# LaunchPad_eZFET_1_4.net
KiCad netlist of a schematic drawn in Altium Designer
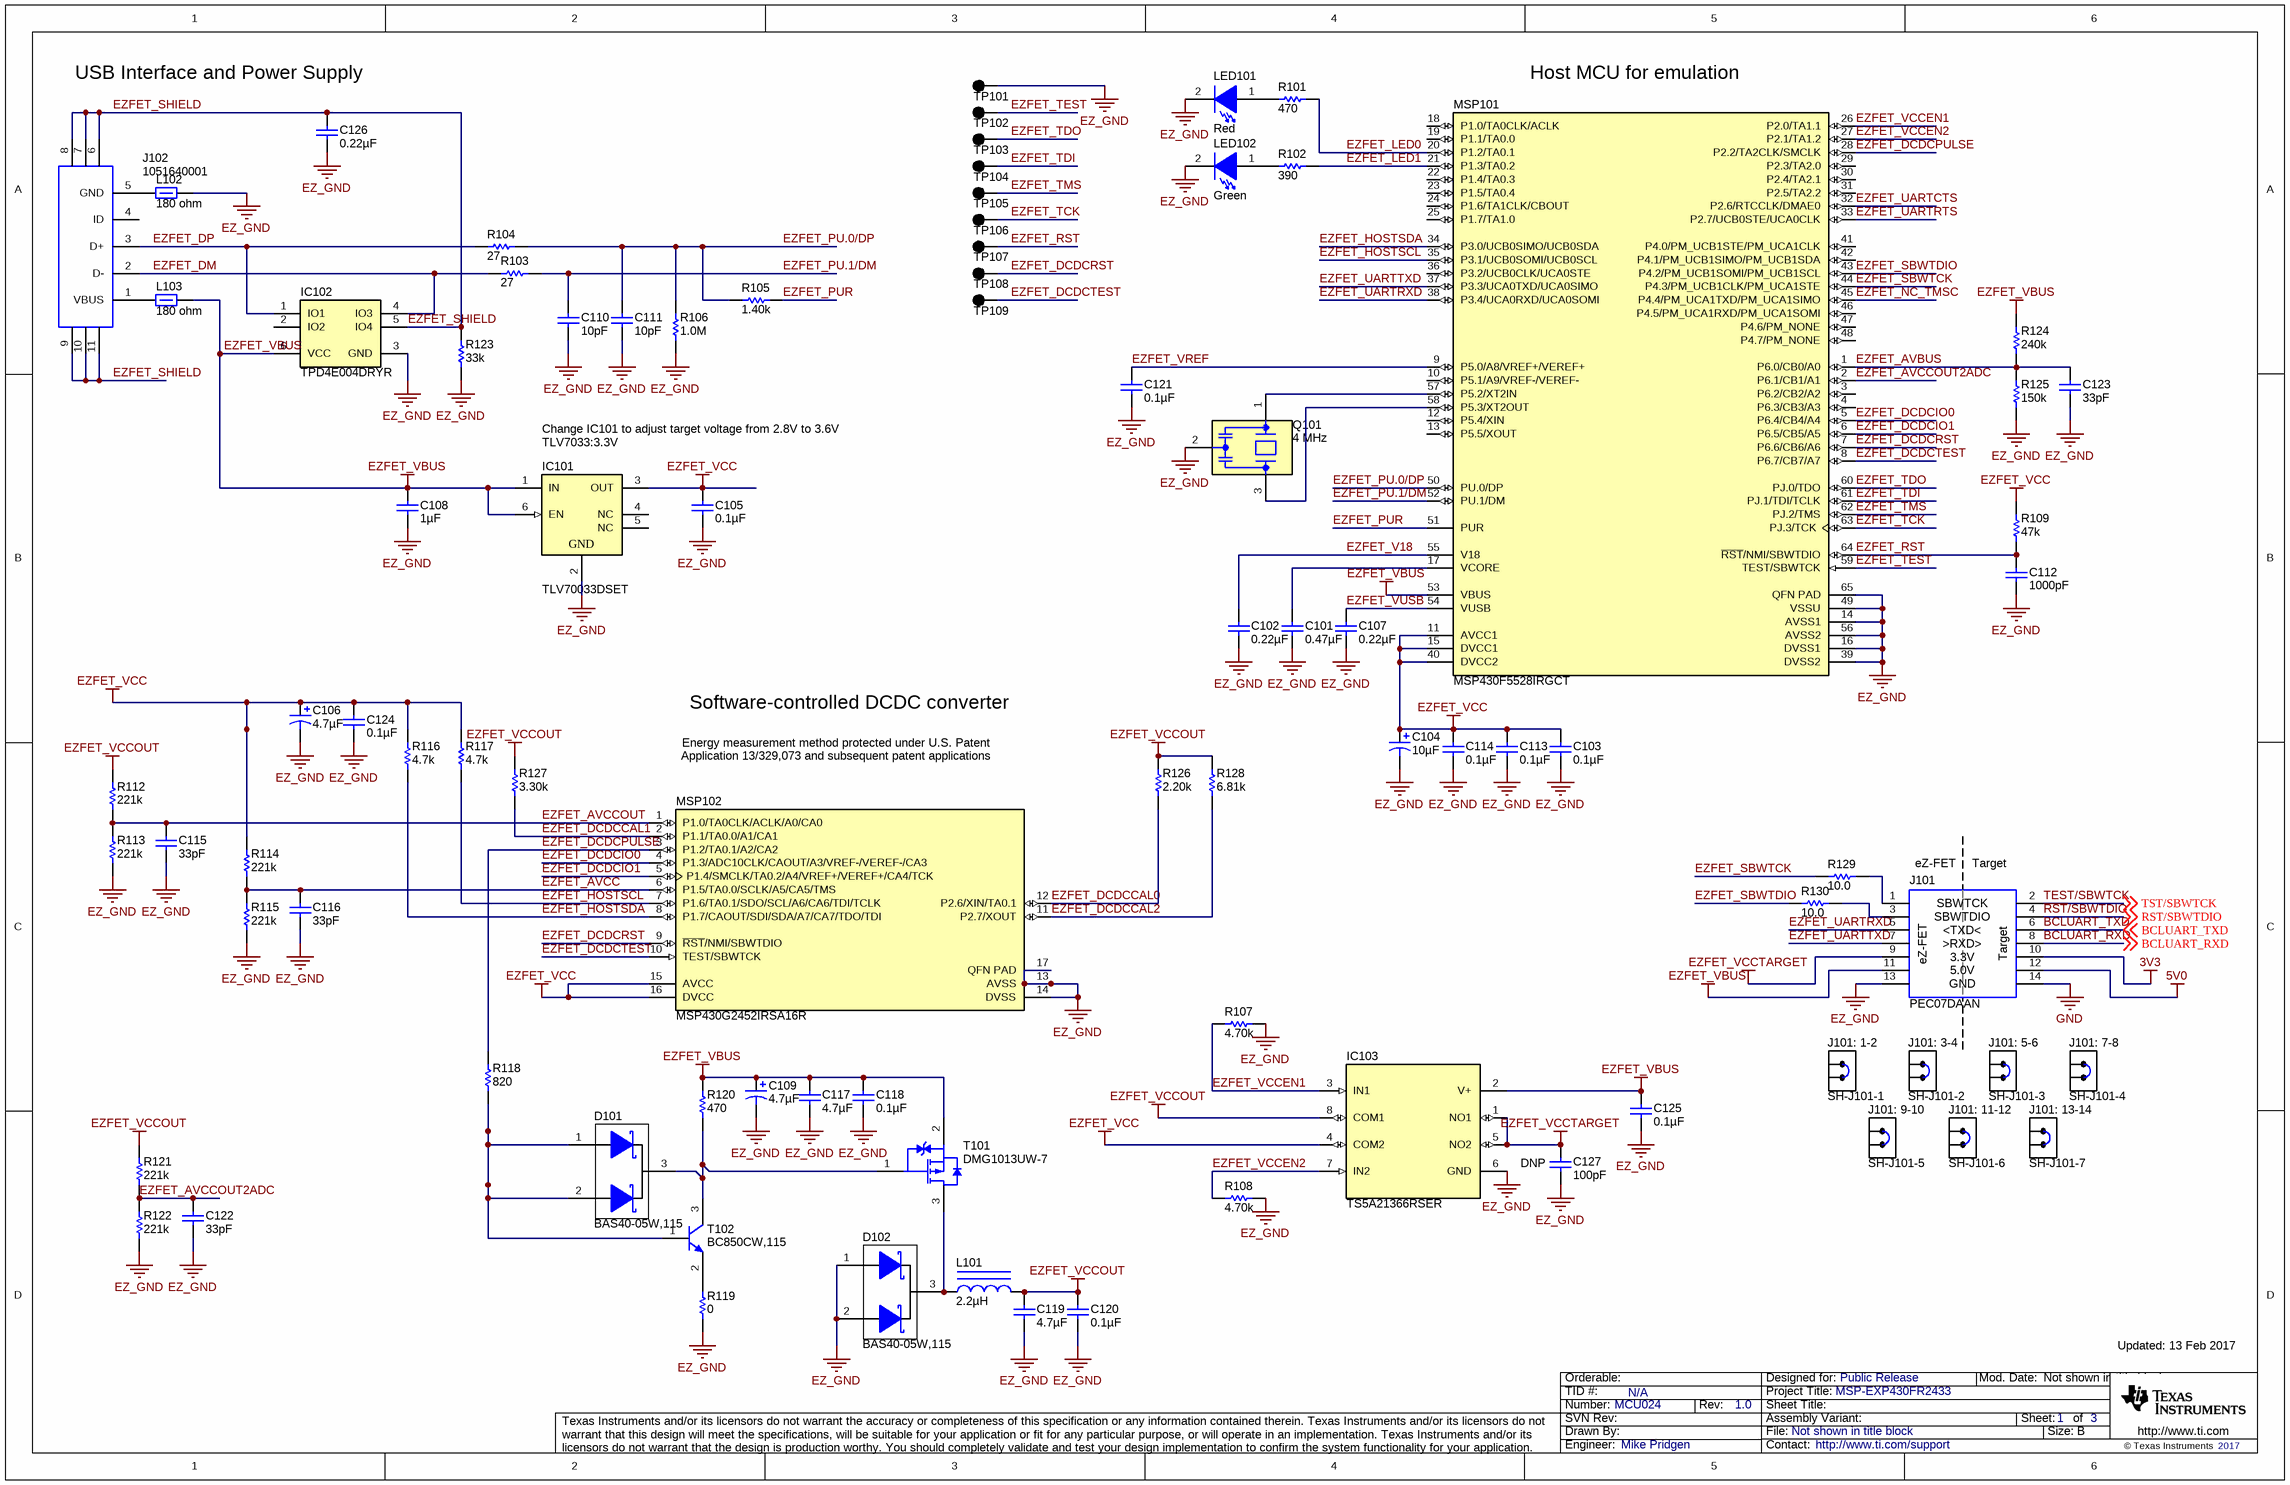
[diagram p0: LaunchPad_eZFET_1.4.SchDoc]

(export (version "E")
  (design (tool "Eeschema 10.0.6"))
  (components
    (comp (ref "C101")
      (value "GRM155R61C474KE01")
      (footprint "0402")
      (description "CAP, CERM, 0.47 µF, 16 V, +/- 10%, X5R, 0402")
      (fields
        (field (name "VALUEDISPLAYED") "0.47µF")
        (field (name "MANUFACTURER") "MuRata")
        (field (name "PUBLISHER") "Texas Instruments")
      )
      (libsource (lib "Capacitor_Ceramic") (part "GRM155R61C474KE01"))
    )
    (comp (ref "C102")
      (value "GRM188R61C224KA88D")
      (footprint "0603")
      (description "CAP, CERM, 0.22 µF, 16 V, +/- 10%, X5R, 0603")
      (fields
        (field (name "VALUEDISPLAYED") "0.22µF")
        (field (name "MANUFACTURER") "MuRata")
        (field (name "PUBLISHER") "Texas Instruments")
      )
      (libsource (lib "Capacitor_Ceramic") (part "GRM188R61C224KA88D"))
    )
    (comp (ref "C103")
      (value "GRM155R61A104KA01D")
      (footprint "0402")
      (description "CAP, CERM, 0.1 µF, 10 V, +/- 10%, X5R, 0402")
      (fields
        (field (name "VALUEDISPLAYED") "0.1µF")
        (field (name "MANUFACTURER") "MuRata")
        (field (name "PUBLISHER") "Texas Instruments")
      )
      (libsource (lib "Capacitor_Ceramic") (part "GRM155R61A104KA01D"))
    )
    (comp (ref "C104")
      (value "293D106X0010A2TE3")
      (footprint "3216-18")
      (description "CAP, TA, 10 µF, 10 V, +/- 20%, 3.4 ohm, SMD")
      (fields
        (field (name "VALUEDISPLAYED") "10µF")
        (field (name "MANUFACTURER") "Vishay-Sprague")
        (field (name "PUBLISHER") "Texas Instruments")
      )
      (libsource (lib "Capacitor_Tantalum") (part "293D106X0010A2TE3"))
    )
    (comp (ref "C105")
      (value "GRM155R61A104KA01D")
      (footprint "0402")
      (description "CAP, CERM, 0.1 µF, 10 V, +/- 10%, X5R, 0402")
      (fields
        (field (name "VALUEDISPLAYED") "0.1µF")
        (field (name "MANUFACTURER") "MuRata")
        (field (name "PUBLISHER") "Texas Instruments")
      )
      (libsource (lib "Capacitor_Ceramic") (part "GRM155R61A104KA01D"))
    )
    (comp (ref "C106")
      (value "293D475X9010A2TE3")
      (footprint "3216-18")
      (description "CAP, TA, 4.7 µF, 10 V, +/- 10%, 5 ohm, SMD")
      (fields
        (field (name "VALUEDISPLAYED") "4.7µF")
        (field (name "MANUFACTURER") "Vishay-Sprague")
        (field (name "PUBLISHER") "Texas Instruments")
      )
      (libsource (lib "Capacitor_Tantalum") (part "293D475X9010A2TE3"))
    )
    (comp (ref "C107")
      (value "GRM188R61C224KA88D")
      (footprint "0603")
      (description "CAP, CERM, 0.22 µF, 16 V, +/- 10%, X5R, 0603")
      (fields
        (field (name "VALUEDISPLAYED") "0.22µF")
        (field (name "MANUFACTURER") "MuRata")
        (field (name "PUBLISHER") "Texas Instruments")
      )
      (libsource (lib "Capacitor_Ceramic") (part "GRM188R61C224KA88D"))
    )
    (comp (ref "C108")
      (value "GRM185R61A105KE36D")
      (footprint "0603")
      (description "CAP, CERM, 1 µF, 10 V, +/- 10%, X5R, 0603")
      (fields
        (field (name "VALUEDISPLAYED") "1µF")
        (field (name "MANUFACTURER") "MuRata")
        (field (name "PUBLISHER") "Texas Instruments")
      )
      (libsource (lib "Capacitor_Ceramic") (part "GRM185R61A105KE36D"))
    )
    (comp (ref "C109")
      (value "293D475X9010A2TE3")
      (footprint "3216-18")
      (description "CAP, TA, 4.7 µF, 10 V, +/- 10%, 5 ohm, SMD")
      (fields
        (field (name "VALUEDISPLAYED") "4.7µF")
        (field (name "MANUFACTURER") "Vishay-Sprague")
        (field (name "PUBLISHER") "Texas Instruments")
      )
      (libsource (lib "Capacitor_Tantalum") (part "293D475X9010A2TE3"))
    )
    (comp (ref "C110")
      (value "GRM1555C1H100JA01D")
      (footprint "0402")
      (description "CAP, CERM, 10 pF, 50 V, +/- 5%, C0G/NP0, 0402")
      (fields
        (field (name "VALUEDISPLAYED") "10pF")
        (field (name "MANUFACTURER") "MuRata")
        (field (name "PUBLISHER") "Texas Instruments")
      )
      (libsource (lib "Capacitor_Ceramic") (part "GRM1555C1H100JA01D"))
    )
    (comp (ref "C111")
      (value "GRM1555C1H100JA01D")
      (footprint "0402")
      (description "CAP, CERM, 10 pF, 50 V, +/- 5%, C0G/NP0, 0402")
      (fields
        (field (name "VALUEDISPLAYED") "10pF")
        (field (name "MANUFACTURER") "MuRata")
        (field (name "PUBLISHER") "Texas Instruments")
      )
      (libsource (lib "Capacitor_Ceramic") (part "GRM1555C1H100JA01D"))
    )
    (comp (ref "C112")
      (value "GRM155R71H102KA01D")
      (footprint "0402")
      (description "CAP, CERM, 1000 pF, 50 V, +/- 10%, X7R, 0402")
      (fields
        (field (name "VALUEDISPLAYED") "1000pF")
        (field (name "MANUFACTURER") "MuRata")
        (field (name "PUBLISHER") "Texas Instruments")
      )
      (libsource (lib "Capacitor_Ceramic") (part "GRM155R71H102KA01D"))
    )
    (comp (ref "C113")
      (value "GRM155R61A104KA01D")
      (footprint "0402")
      (description "CAP, CERM, 0.1 µF, 10 V, +/- 10%, X5R, 0402")
      (fields
        (field (name "VALUEDISPLAYED") "0.1µF")
        (field (name "MANUFACTURER") "MuRata")
        (field (name "PUBLISHER") "Texas Instruments")
      )
      (libsource (lib "Capacitor_Ceramic") (part "GRM155R61A104KA01D"))
    )
    (comp (ref "C114")
      (value "GRM155R61A104KA01D")
      (footprint "0402")
      (description "CAP, CERM, 0.1 µF, 10 V, +/- 10%, X5R, 0402")
      (fields
        (field (name "VALUEDISPLAYED") "0.1µF")
        (field (name "MANUFACTURER") "MuRata")
        (field (name "PUBLISHER") "Texas Instruments")
      )
      (libsource (lib "Capacitor_Ceramic") (part "GRM155R61A104KA01D"))
    )
    (comp (ref "C115")
      (value "GRM1555C1H330JA01D")
      (footprint "0402")
      (description "CAP, CERM, 33 pF, 50 V, +/- 5%, C0G/NP0, 0402")
      (fields
        (field (name "VALUEDISPLAYED") "33pF")
        (field (name "MANUFACTURER") "MuRata")
        (field (name "PUBLISHER") "Texas Instruments")
      )
      (libsource (lib "Capacitor_Ceramic") (part "GRM1555C1H330JA01D"))
    )
    (comp (ref "C116")
      (value "GRM1555C1H330JA01D")
      (footprint "0402")
      (description "CAP, CERM, 33 pF, 50 V, +/- 5%, C0G/NP0, 0402")
      (fields
        (field (name "VALUEDISPLAYED") "33pF")
        (field (name "MANUFACTURER") "MuRata")
        (field (name "PUBLISHER") "Texas Instruments")
      )
      (libsource (lib "Capacitor_Ceramic") (part "GRM1555C1H330JA01D"))
    )
    (comp (ref "C117")
      (value "GRM188R61C475KAAJ")
      (footprint "0603")
      (description "CAP, CERM, 4.7 µF, 16 V, +/- 10%, X5R, 0603")
      (fields
        (field (name "VALUEDISPLAYED") "4.7µF")
        (field (name "MANUFACTURER") "MuRata")
        (field (name "PUBLISHER") "Texas Instruments")
      )
      (libsource (lib "Capacitor_Ceramic") (part "GRM188R61C475KAAJ"))
    )
    (comp (ref "C118")
      (value "GRM155R61A104KA01D")
      (footprint "0402")
      (description "CAP, CERM, 0.1 µF, 10 V, +/- 10%, X5R, 0402")
      (fields
        (field (name "VALUEDISPLAYED") "0.1µF")
        (field (name "MANUFACTURER") "MuRata")
        (field (name "PUBLISHER") "Texas Instruments")
      )
      (libsource (lib "Capacitor_Ceramic") (part "GRM155R61A104KA01D"))
    )
    (comp (ref "C119")
      (value "GRM188R61C475KAAJ")
      (footprint "0603")
      (description "CAP, CERM, 4.7 µF, 16 V, +/- 10%, X5R, 0603")
      (fields
        (field (name "VALUEDISPLAYED") "4.7µF")
        (field (name "MANUFACTURER") "MuRata")
        (field (name "PUBLISHER") "Texas Instruments")
      )
      (libsource (lib "Capacitor_Ceramic") (part "GRM188R61C475KAAJ"))
    )
    (comp (ref "C120")
      (value "GRM155R61A104KA01D")
      (footprint "0402")
      (description "CAP, CERM, 0.1 µF, 10 V, +/- 10%, X5R, 0402")
      (fields
        (field (name "VALUEDISPLAYED") "0.1µF")
        (field (name "MANUFACTURER") "MuRata")
        (field (name "PUBLISHER") "Texas Instruments")
      )
      (libsource (lib "Capacitor_Ceramic") (part "GRM155R61A104KA01D"))
    )
    (comp (ref "C121")
      (value "GRM155R61A104KA01D")
      (footprint "0402")
      (description "CAP, CERM, 0.1 µF, 10 V, +/- 10%, X5R, 0402")
      (fields
        (field (name "VALUEDISPLAYED") "0.1µF")
        (field (name "MANUFACTURER") "MuRata")
        (field (name "PUBLISHER") "Texas Instruments")
      )
      (libsource (lib "Capacitor_Ceramic") (part "GRM155R61A104KA01D"))
    )
    (comp (ref "C122")
      (value "GRM1555C1H330JA01D")
      (footprint "0402")
      (description "CAP, CERM, 33 pF, 50 V, +/- 5%, C0G/NP0, 0402")
      (fields
        (field (name "VALUEDISPLAYED") "33pF")
        (field (name "MANUFACTURER") "MuRata")
        (field (name "PUBLISHER") "Texas Instruments")
      )
      (libsource (lib "Capacitor_Ceramic") (part "GRM1555C1H330JA01D"))
    )
    (comp (ref "C123")
      (value "GRM1555C1H330JA01D")
      (footprint "0402")
      (description "CAP, CERM, 33 pF, 50 V, +/- 5%, C0G/NP0, 0402")
      (fields
        (field (name "VALUEDISPLAYED") "33pF")
        (field (name "MANUFACTURER") "MuRata")
        (field (name "PUBLISHER") "Texas Instruments")
      )
      (libsource (lib "Capacitor_Ceramic") (part "GRM1555C1H330JA01D"))
    )
    (comp (ref "C124")
      (value "GRM155R61A104KA01D")
      (footprint "0402")
      (description "CAP, CERM, 0.1 µF, 10 V, +/- 10%, X5R, 0402")
      (fields
        (field (name "VALUEDISPLAYED") "0.1µF")
        (field (name "MANUFACTURER") "MuRata")
        (field (name "PUBLISHER") "Texas Instruments")
      )
      (libsource (lib "Capacitor_Ceramic") (part "GRM155R61A104KA01D"))
    )
    (comp (ref "C125")
      (value "GRM155R61A104KA01D")
      (footprint "0402")
      (description "CAP, CERM, 0.1 µF, 10 V, +/- 10%, X5R, 0402")
      (fields
        (field (name "VALUEDISPLAYED") "0.1µF")
        (field (name "MANUFACTURER") "MuRata")
        (field (name "PUBLISHER") "Texas Instruments")
      )
      (libsource (lib "Capacitor_Ceramic") (part "GRM155R61A104KA01D"))
    )
    (comp (ref "C126")
      (value "GRM155R61A224KE19D")
      (footprint "0402")
      (description "CAP, CERM, 0.22 µF, 10 V, +/- 10%, X5R, 0402")
      (fields
        (field (name "VALUEDISPLAYED") "0.22µF")
        (field (name "MANUFACTURER") "MuRata")
        (field (name "PUBLISHER") "Texas Instruments")
      )
      (libsource (lib "Capacitor_Ceramic") (part "GRM155R61A224KE19D"))
    )
    (comp (ref "C127")
      (value "GRM1555C1H101JA01D")
      (footprint "0402")
      (description "CAP, CERM, 100 pF, 50 V, +/- 5%, C0G/NP0, 0402")
      (fields
        (field (name "VALUEDISPLAYED") "100pF")
        (field (name "MANUFACTURER") "MuRata")
        (field (name "NOTE") "DNP")
        (field (name "PUBLISHER") "Texas Instruments")
      )
      (libsource (lib "Capacitor_Ceramic") (part "GRM1555C1H101JA01D"))
    )
    (comp (ref "D101")
      (value "BAS40-05W,115")
      (footprint "SOT-323")
      (description "Diode, Schottky, 40 V, 0.12 A, AEC-Q101, SOT-323")
      (fields
        (field (name "MANUFACTURER") "NXP Semiconductor")
        (field (name "SYMBOLCREATOR") "a0412235")
        (field (name "PUBLISHER") "Texas Instruments")
      )
      (libsource (lib "Diode") (part "BAS40-05W,115"))
    )
    (comp (ref "D102")
      (value "BAS40-05W,115")
      (footprint "SOT-323")
      (description "Diode, Schottky, 40 V, 0.12 A, AEC-Q101, SOT-323")
      (fields
        (field (name "MANUFACTURER") "NXP Semiconductor")
        (field (name "SYMBOLCREATOR") "a0412235")
        (field (name "PUBLISHER") "Texas Instruments")
      )
      (libsource (lib "Diode") (part "BAS40-05W,115"))
    )
    (comp (ref "IC101")
      (value "TLV70033DSET")
      (footprint "DSE0006A")
      (fields
        (field (name "MANUFACTURER") "Texas Instruments")
        (field (name "ALTERNATE PARTNUMBER") "Equivalent")
      )
      (libsource (lib "TI Power Management Linear Regulator Single Channel LDO (0-350mA)") (part "TLV70033DSET"))
    )
    (comp (ref "IC102")
      (value "TPD4E004DRYR")
      (footprint "DRY0006A")
      (fields
        (field (name "MANUFACTURER") "Texas Instruments")
        (field (name "ALTERNATE PARTNUMBER") "Equivalent")
      )
      (libsource (lib "TI Interface ESD EMI Protection") (part "TPD4E004DRYR"))
    )
    (comp (ref "IC103")
      (value "TS5A21366RSER")
      (footprint "RSE0008A")
      (description "0.75-Ohm DUAL SPST ANALOG SWITCH WITH 1.8-V COMPATIBLE INPUT LOGIC, RSE0008A (UQFN-8)")
      (fields
        (field (name "MANUFACTURER") "Texas Instruments")
        (field (name "SYMBOLCREATOR") "a0411947")
        (field (name "PUBLISHER") "Texas Instruments")
      )
      (libsource (lib "TI_Pre_Release1") (part "TS5A21366RSER"))
    )
    (comp (ref "J101")
      (value "PEC07DAAN")
      (footprint "PEC07DAAN_Launchpad_EZ-FET")
      (description "Header, 100mil, 7x2, Tin, TH")
      (fields
        (field (name "MANUFACTURER") "Sullins Connector Solutions")
        (field (name "SYMBOLCREATOR") "a0412235")
        (field (name "PUBLISHER") "Texas Instruments")
      )
      (libsource (lib "Connectors_Sullins") (part "PEC07DAAN"))
    )
    (comp (ref "J102")
      (value "1051640001")
      (footprint "Molex_1051640001")
      (description "Receptacle, USB 2.0, Micro B, 5 Position, R/A, SMT")
      (fields
        (field (name "MANUFACTURER") "Molex")
        (field (name "SYMBOLCREATOR") "a0411947")
        (field (name "PUBLISHER") "Texas Instruments")
      )
      (libsource (lib "Connectors_Molex") (part "1051640001"))
    )
    (comp (ref "L101")
      (value "CBC2518T2R2M")
      (footprint "CBC2518")
      (description "Inductor, Wirewound, Ceramic, 2.2 µH, 0.89 A, 0.13 ohm, SMD")
      (fields
        (field (name "VALUEDISPLAYED") "2.2µH")
        (field (name "MANUFACTURER") "Taiyo Yuden")
        (field (name "PUBLISHER") "Texas Instruments")
      )
      (libsource (lib "Inductor_Other") (part "CBC2518T2R2M"))
    )
    (comp (ref "L102")
      (value "742792622")
      (footprint "0603")
      (description "Ferrite Bead, 180 ohm @ 100 MHz, 0.5 A, 0603")
      (fields
        (field (name "VALUEDISPLAYED") "180 ohm")
        (field (name "MANUFACTURER") "Wurth Elektronik")
        (field (name "PUBLISHER") "Texas Instruments")
      )
      (libsource (lib "FerriteBead") (part "742792622"))
    )
    (comp (ref "L103")
      (value "742792622")
      (footprint "0603")
      (description "Ferrite Bead, 180 ohm @ 100 MHz, 0.5 A, 0603")
      (fields
        (field (name "VALUEDISPLAYED") "180 ohm")
        (field (name "MANUFACTURER") "Wurth Elektronik")
        (field (name "PUBLISHER") "Texas Instruments")
      )
      (libsource (lib "FerriteBead") (part "742792622"))
    )
    (comp (ref "LED101")
      (value "Red")
      (footprint "LED_LTST-C190_Red")
      (description "LED, Red, SMD")
      (fields
        (field (name "MANUFACTURER") "Lite-On")
        (field (name "PARTNUMBER") "LTST-C190CKT")
        (field (name "PUBLISHER") "Texas Instruments")
      )
      (libsource (lib "LED") (part "LTST-C190CKT"))
    )
    (comp (ref "LED102")
      (value "Green")
      (footprint "LED_LTST-C190")
      (description "LED, Green, SMD")
      (fields
        (field (name "MANUFACTURER") "Lite-On")
        (field (name "PARTNUMBER") "LTST-C190GKT")
        (field (name "PUBLISHER") "Texas Instruments")
      )
      (libsource (lib "LED") (part "LTST-C190GKT"))
    )
    (comp (ref "MSP101")
      (value "MSP430F5528IRGCT")
      (footprint "RGC0064B")
      (fields
        (field (name "ALTERNATE PARTNUMBER") "Equivalent")
        (field (name "MANUFACTURER") "Texas Instruments")
      )
      (libsource (lib "TI MCU MSP430") (part "MSP430F5528IRGCT"))
    )
    (comp (ref "MSP102")
      (value "MSP430G2452IRSA16R")
      (footprint "RSA0016B")
      (fields
        (field (name "ALTERNATE PARTNUMBER") "Equivalent")
        (field (name "MANUFACTURER") "Texas Instruments")
      )
      (libsource (lib "TI MCU MSP430") (part "MSP430G2452IRSA16R"))
    )
    (comp (ref "Q101")
      (value "CSTCR4M00G15L99-R0")
      (footprint "Murata_CSTCR")
      (description "Resonator, 4MHz, 39pF SMD")
      (fields
        (field (name "FREQUENCY") "4 MHz")
        (field (name "MANUFACTURER") "MuRata")
        (field (name "SYMBOLCREATOR") "a0799721")
        (field (name "PUBLISHER") "Texas Instruments")
      )
      (libsource (lib "Oscillators") (part "CSTCR4M00G15L99-R0"))
    )
    (comp (ref "R101")
      (value "CRCW0402470RJNED")
      (footprint "0402")
      (description "RES, 470, 5%, 0.063 W, 0402")
      (fields
        (field (name "VALUEDISPLAYED") "470")
        (field (name "MANUFACTURER") "Vishay-Dale")
        (field (name "PUBLISHER") "Texas Instruments")
      )
      (libsource (lib "Resistor_0402") (part "CRCW0402470RJNED"))
    )
    (comp (ref "R102")
      (value "CRCW0402390RJNED")
      (footprint "0402")
      (description "RES, 390, 5%, 0.063 W, 0402")
      (fields
        (field (name "VALUEDISPLAYED") "390")
        (field (name "MANUFACTURER") "Vishay-Dale")
        (field (name "PUBLISHER") "Texas Instruments")
      )
      (libsource (lib "Resistor_0402") (part "CRCW0402390RJNED"))
    )
    (comp (ref "R103")
      (value "CRCW040227R0JNED")
      (footprint "0402")
      (description "RES, 27, 5%, 0.063 W, 0402")
      (fields
        (field (name "VALUEDISPLAYED") "27")
        (field (name "MANUFACTURER") "Vishay-Dale")
        (field (name "PUBLISHER") "Texas Instruments")
      )
      (libsource (lib "Resistor_0402") (part "CRCW040227R0JNED"))
    )
    (comp (ref "R104")
      (value "CRCW040227R0JNED")
      (footprint "0402")
      (description "RES, 27, 5%, 0.063 W, 0402")
      (fields
        (field (name "VALUEDISPLAYED") "27")
        (field (name "MANUFACTURER") "Vishay-Dale")
        (field (name "PUBLISHER") "Texas Instruments")
      )
      (libsource (lib "Resistor_0402") (part "CRCW040227R0JNED"))
    )
    (comp (ref "R105")
      (value "CRCW04021K40FKED")
      (footprint "0402")
      (description "RES, 1.40 k, 1%, 0.063 W, 0402")
      (fields
        (field (name "VALUEDISPLAYED") "1.40k")
        (field (name "MANUFACTURER") "Vishay-Dale")
        (field (name "PUBLISHER") "Texas Instruments")
      )
      (libsource (lib "Resistor_0402") (part "CRCW04021K40FKED"))
    )
    (comp (ref "R106")
      (value "CRCW04021M00JNED")
      (footprint "0402")
      (description "RES, 1.0 M, 5%, 0.063 W, 0402")
      (fields
        (field (name "VALUEDISPLAYED") "1.0M")
        (field (name "MANUFACTURER") "Vishay-Dale")
        (field (name "PUBLISHER") "Texas Instruments")
      )
      (libsource (lib "Resistor_0402") (part "CRCW04021M00JNED"))
    )
    (comp (ref "R107")
      (value "CRG0402F4K7")
      (footprint "0402")
      (description "RES, 4.70 k, 1%, 0.063 W, 0402")
      (fields
        (field (name "VALUEDISPLAYED") "4.70k")
        (field (name "MANUFACTURER") "TE Connectivity")
        (field (name "PUBLISHER") "Texas Instruments")
      )
      (libsource (lib "Resistor_0402") (part "CRG0402F4K7"))
    )
    (comp (ref "R108")
      (value "CRG0402F4K7")
      (footprint "0402")
      (description "RES, 4.70 k, 1%, 0.063 W, 0402")
      (fields
        (field (name "VALUEDISPLAYED") "4.70k")
        (field (name "MANUFACTURER") "TE Connectivity")
        (field (name "PUBLISHER") "Texas Instruments")
      )
      (libsource (lib "Resistor_0402") (part "CRG0402F4K7"))
    )
    (comp (ref "R109")
      (value "CRCW040247K0JNED")
      (footprint "0402")
      (description "RES, 47 k, 5%, 0.063 W, 0402")
      (fields
        (field (name "VALUEDISPLAYED") "47k")
        (field (name "MANUFACTURER") "Vishay-Dale")
        (field (name "PUBLISHER") "Texas Instruments")
      )
      (libsource (lib "Resistor_0402") (part "CRCW040247K0JNED"))
    )
    (comp (ref "R112")
      (value "CRCW0402221KFKED")
      (footprint "0402")
      (description "RES, 221 k, 1%, 0.063 W, 0402")
      (fields
        (field (name "VALUEDISPLAYED") "221k")
        (field (name "MANUFACTURER") "Vishay-Dale")
        (field (name "PUBLISHER") "Texas Instruments")
      )
      (libsource (lib "Resistor_0402") (part "CRCW0402221KFKED"))
    )
    (comp (ref "R113")
      (value "CRCW0402221KFKED")
      (footprint "0402")
      (description "RES, 221 k, 1%, 0.063 W, 0402")
      (fields
        (field (name "VALUEDISPLAYED") "221k")
        (field (name "MANUFACTURER") "Vishay-Dale")
        (field (name "PUBLISHER") "Texas Instruments")
      )
      (libsource (lib "Resistor_0402") (part "CRCW0402221KFKED"))
    )
    (comp (ref "R114")
      (value "CRCW0402221KFKED")
      (footprint "0402")
      (description "RES, 221 k, 1%, 0.063 W, 0402")
      (fields
        (field (name "VALUEDISPLAYED") "221k")
        (field (name "MANUFACTURER") "Vishay-Dale")
        (field (name "PUBLISHER") "Texas Instruments")
      )
      (libsource (lib "Resistor_0402") (part "CRCW0402221KFKED"))
    )
    (comp (ref "R115")
      (value "CRCW0402221KFKED")
      (footprint "0402")
      (description "RES, 221 k, 1%, 0.063 W, 0402")
      (fields
        (field (name "VALUEDISPLAYED") "221k")
        (field (name "MANUFACTURER") "Vishay-Dale")
        (field (name "PUBLISHER") "Texas Instruments")
      )
      (libsource (lib "Resistor_0402") (part "CRCW0402221KFKED"))
    )
    (comp (ref "R116")
      (value "CRCW04024K70JNED")
      (footprint "0402")
      (description "RES, 4.7 k, 5%, 0.063 W, 0402")
      (fields
        (field (name "VALUEDISPLAYED") "4.7k")
        (field (name "MANUFACTURER") "Vishay-Dale")
        (field (name "PUBLISHER") "Texas Instruments")
      )
      (libsource (lib "Resistor_0402") (part "CRCW04024K70JNED"))
    )
    (comp (ref "R117")
      (value "CRCW04024K70JNED")
      (footprint "0402")
      (description "RES, 4.7 k, 5%, 0.063 W, 0402")
      (fields
        (field (name "VALUEDISPLAYED") "4.7k")
        (field (name "MANUFACTURER") "Vishay-Dale")
        (field (name "PUBLISHER") "Texas Instruments")
      )
      (libsource (lib "Resistor_0402") (part "CRCW04024K70JNED"))
    )
    (comp (ref "R118")
      (value "RC0402FR-07820RL")
      (footprint "0402")
      (description "RES, 820, 1%, 0.063 W, 0402")
      (fields
        (field (name "VALUEDISPLAYED") "820")
        (field (name "MANUFACTURER") "Yageo America")
        (field (name "PUBLISHER") "Texas Instruments")
      )
      (libsource (lib "Resistor_0402") (part "RC0402FR-07820RL"))
    )
    (comp (ref "R119")
      (value "CRCW04020000Z0ED")
      (footprint "0402")
      (description "RES, 0, 5%, 0.063 W, 0402")
      (fields
        (field (name "VALUEDISPLAYED") "0")
        (field (name "MANUFACTURER") "Vishay-Dale")
        (field (name "PUBLISHER") "Texas Instruments")
      )
      (libsource (lib "Resistor_0402") (part "CRCW04020000Z0ED"))
    )
    (comp (ref "R120")
      (value "CRCW0402470RJNED")
      (footprint "0402")
      (description "RES, 470, 5%, 0.063 W, 0402")
      (fields
        (field (name "VALUEDISPLAYED") "470")
        (field (name "MANUFACTURER") "Vishay-Dale")
        (field (name "PUBLISHER") "Texas Instruments")
      )
      (libsource (lib "Resistor_0402") (part "CRCW0402470RJNED"))
    )
    (comp (ref "R121")
      (value "CRCW0402221KFKED")
      (footprint "0402")
      (description "RES, 221 k, 1%, 0.063 W, 0402")
      (fields
        (field (name "VALUEDISPLAYED") "221k")
        (field (name "MANUFACTURER") "Vishay-Dale")
        (field (name "PUBLISHER") "Texas Instruments")
      )
      (libsource (lib "Resistor_0402") (part "CRCW0402221KFKED"))
    )
    (comp (ref "R122")
      (value "CRCW0402221KFKED")
      (footprint "0402")
      (description "RES, 221 k, 1%, 0.063 W, 0402")
      (fields
        (field (name "VALUEDISPLAYED") "221k")
        (field (name "MANUFACTURER") "Vishay-Dale")
        (field (name "PUBLISHER") "Texas Instruments")
      )
      (libsource (lib "Resistor_0402") (part "CRCW0402221KFKED"))
    )
    (comp (ref "R123")
      (value "CRCW040233K0JNED")
      (footprint "0402")
      (description "RES, 33 k, 5%, 0.063 W, 0402")
      (fields
        (field (name "VALUEDISPLAYED") "33k")
        (field (name "MANUFACTURER") "Vishay-Dale")
        (field (name "PUBLISHER") "Texas Instruments")
      )
      (libsource (lib "Resistor_0402") (part "CRCW040233K0JNED"))
    )
    (comp (ref "R124")
      (value "CRCW0402240KFKED")
      (footprint "0402")
      (description "RES, 240 k, 1%, 0.063 W, 0402")
      (fields
        (field (name "VALUEDISPLAYED") "240k")
        (field (name "MANUFACTURER") "Vishay-Dale")
        (field (name "PUBLISHER") "Texas Instruments")
      )
      (libsource (lib "Resistor_0402") (part "CRCW0402240KFKED"))
    )
    (comp (ref "R125")
      (value "CRCW0402150KFKED")
      (footprint "0402")
      (description "RES, 150 k, 1%, 0.063 W, 0402")
      (fields
        (field (name "VALUEDISPLAYED") "150k")
        (field (name "MANUFACTURER") "Vishay-Dale")
        (field (name "PUBLISHER") "Texas Instruments")
      )
      (libsource (lib "Resistor_0402") (part "CRCW0402150KFKED"))
    )
    (comp (ref "R126")
      (value "CRCW04022K20FKED")
      (footprint "0402")
      (description "RES, 2.20 k, 1%, 0.063 W, 0402")
      (fields
        (field (name "VALUEDISPLAYED") "2.20k")
        (field (name "MANUFACTURER") "Vishay-Dale")
        (field (name "PUBLISHER") "Texas Instruments")
      )
      (libsource (lib "Resistor_0402") (part "CRCW04022K20FKED"))
    )
    (comp (ref "R127")
      (value "ERJ-2RKF3301X")
      (footprint "0402")
      (description "RES, 3.30 k, 1%, 0.1 W, AEC-Q200 Grade 0, 0402")
      (fields
        (field (name "VALUEDISPLAYED") "3.30k")
        (field (name "MANUFACTURER") "Panasonic")
        (field (name "PUBLISHER") "Texas Instruments")
      )
      (libsource (lib "Resistor_0402") (part "ERJ-2RKF3301X"))
    )
    (comp (ref "R128")
      (value "CRCW04026K81FKED")
      (footprint "0402")
      (description "RES, 6.81 k, 1%, 0.063 W, 0402")
      (fields
        (field (name "VALUEDISPLAYED") "6.81k")
        (field (name "MANUFACTURER") "Vishay-Dale")
        (field (name "PUBLISHER") "Texas Instruments")
      )
      (libsource (lib "Resistor_0402") (part "CRCW04026K81FKED"))
    )
    (comp (ref "R129")
      (value "CRCW040210R0FKED")
      (footprint "0402")
      (description "RES, 10.0, 1%, 0.063 W, 0402")
      (fields
        (field (name "VALUEDISPLAYED") "10.0")
        (field (name "MANUFACTURER") "Vishay-Dale")
        (field (name "PUBLISHER") "Texas Instruments")
      )
      (libsource (lib "Resistor_0402") (part "CRCW040210R0FKED"))
    )
    (comp (ref "R130")
      (value "CRCW040210R0FKED")
      (footprint "0402")
      (description "RES, 10.0, 1%, 0.063 W, 0402")
      (fields
        (field (name "VALUEDISPLAYED") "10.0")
        (field (name "MANUFACTURER") "Vishay-Dale")
        (field (name "PUBLISHER") "Texas Instruments")
      )
      (libsource (lib "Resistor_0402") (part "CRCW040210R0FKED"))
    )
    (comp (ref "SH-J101-1")
      (value "SNT-100-BK-G")
      (footprint "SNT-100-BK-G")
      (description "Shunt, 100mil, Gold plated, Black")
      (fields
        (field (name "MANUFACTURER") "Samtec")
        (field (name "NOTE") "J101: 1-2")
        (field (name "ALTERNATE PARTNUMBER") "969102-0000-DA")
        (field (name "PUBLISHER") "Texas Instruments")
      )
      (libsource (lib "Hardware") (part "SNT-100-BK-G"))
    )
    (comp (ref "SH-J101-2")
      (value "SNT-100-BK-G")
      (footprint "SNT-100-BK-G")
      (description "Shunt, 100mil, Gold plated, Black")
      (fields
        (field (name "MANUFACTURER") "Samtec")
        (field (name "NOTE") "J101: 3-4")
        (field (name "ALTERNATE PARTNUMBER") "969102-0000-DA")
        (field (name "PUBLISHER") "Texas Instruments")
      )
      (libsource (lib "Hardware") (part "SNT-100-BK-G"))
    )
    (comp (ref "SH-J101-3")
      (value "SNT-100-BK-G")
      (footprint "SNT-100-BK-G")
      (description "Shunt, 100mil, Gold plated, Black")
      (fields
        (field (name "MANUFACTURER") "Samtec")
        (field (name "NOTE") "J101: 5-6")
        (field (name "ALTERNATE PARTNUMBER") "969102-0000-DA")
        (field (name "PUBLISHER") "Texas Instruments")
      )
      (libsource (lib "Hardware") (part "SNT-100-BK-G"))
    )
    (comp (ref "SH-J101-4")
      (value "SNT-100-BK-G")
      (footprint "SNT-100-BK-G")
      (description "Shunt, 100mil, Gold plated, Black")
      (fields
        (field (name "MANUFACTURER") "Samtec")
        (field (name "NOTE") "J101: 7-8")
        (field (name "ALTERNATE PARTNUMBER") "969102-0000-DA")
        (field (name "PUBLISHER") "Texas Instruments")
      )
      (libsource (lib "Hardware") (part "SNT-100-BK-G"))
    )
    (comp (ref "SH-J101-5")
      (value "SNT-100-BK-G")
      (footprint "SNT-100-BK-G")
      (description "Shunt, 100mil, Gold plated, Black")
      (fields
        (field (name "MANUFACTURER") "Samtec")
        (field (name "NOTE") "J101: 9-10")
        (field (name "ALTERNATE PARTNUMBER") "969102-0000-DA")
        (field (name "PUBLISHER") "Texas Instruments")
      )
      (libsource (lib "Hardware") (part "SNT-100-BK-G"))
    )
    (comp (ref "SH-J101-6")
      (value "SNT-100-BK-G")
      (footprint "SNT-100-BK-G")
      (description "Shunt, 100mil, Gold plated, Black")
      (fields
        (field (name "MANUFACTURER") "Samtec")
        (field (name "NOTE") "J101: 11-12")
        (field (name "ALTERNATE PARTNUMBER") "969102-0000-DA")
        (field (name "PUBLISHER") "Texas Instruments")
      )
      (libsource (lib "Hardware") (part "SNT-100-BK-G"))
    )
    (comp (ref "SH-J101-7")
      (value "SNT-100-BK-G")
      (footprint "SNT-100-BK-G")
      (description "Shunt, 100mil, Gold plated, Black")
      (fields
        (field (name "MANUFACTURER") "Samtec")
        (field (name "NOTE") "J101: 13-14")
        (field (name "ALTERNATE PARTNUMBER") "969102-0000-DA")
        (field (name "PUBLISHER") "Texas Instruments")
      )
      (libsource (lib "Hardware") (part "SNT-100-BK-G"))
    )
    (comp (ref "T101")
      (value "DMG1013UW-7")
      (footprint "SOT-323")
      (description "MOSFET, P-CH, -20 V, -0.82 A, SOT-323")
      (fields
        (field (name "MANUFACTURER") "Diodes Inc.")
        (field (name "SYMBOLCREATOR") "a0411947")
        (field (name "PUBLISHER") "Texas Instruments")
      )
      (libsource (lib "FETs") (part "DMG1013UW-7"))
    )
    (comp (ref "T102")
      (value "BC850CW,115")
      (footprint "SOT-323")
      (description "Transistor, NPN, 45 V, 0.1 A, SOT-323")
      (fields
        (field (name "MANUFACTURER") "NXP Semiconductor")
        (field (name "PUBLISHER") "Texas Instruments")
      )
      (libsource (lib "Bipolar_Transistor") (part "BC850CW,115, NXP Semiconductor"))
    )
    (comp (ref "TP101")
      (value "5001")
      (footprint "Keystone5001")
      (description "Test Point, Miniature, Black, TH")
      (fields (field (name "MANUFACTURER") "Keystone") (field (name "PUBLISHER") "Texas Instruments"))
      (libsource (lib "Connectors_Keystone") (part "5001"))
    )
    (comp (ref "TP102")
      (value "5001")
      (footprint "Keystone5001")
      (description "Test Point, Miniature, Black, TH")
      (fields (field (name "MANUFACTURER") "Keystone") (field (name "PUBLISHER") "Texas Instruments"))
      (libsource (lib "Connectors_Keystone") (part "5001"))
    )
    (comp (ref "TP103")
      (value "5001")
      (footprint "Keystone5001")
      (description "Test Point, Miniature, Black, TH")
      (fields (field (name "MANUFACTURER") "Keystone") (field (name "PUBLISHER") "Texas Instruments"))
      (libsource (lib "Connectors_Keystone") (part "5001"))
    )
    (comp (ref "TP104")
      (value "5001")
      (footprint "Keystone5001")
      (description "Test Point, Miniature, Black, TH")
      (fields (field (name "MANUFACTURER") "Keystone") (field (name "PUBLISHER") "Texas Instruments"))
      (libsource (lib "Connectors_Keystone") (part "5001"))
    )
    (comp (ref "TP105")
      (value "5001")
      (footprint "Keystone5001")
      (description "Test Point, Miniature, Black, TH")
      (fields (field (name "MANUFACTURER") "Keystone") (field (name "PUBLISHER") "Texas Instruments"))
      (libsource (lib "Connectors_Keystone") (part "5001"))
    )
    (comp (ref "TP106")
      (value "5001")
      (footprint "Keystone5001")
      (description "Test Point, Miniature, Black, TH")
      (fields (field (name "MANUFACTURER") "Keystone") (field (name "PUBLISHER") "Texas Instruments"))
      (libsource (lib "Connectors_Keystone") (part "5001"))
    )
    (comp (ref "TP107")
      (value "5001")
      (footprint "Keystone5001")
      (description "Test Point, Miniature, Black, TH")
      (fields (field (name "MANUFACTURER") "Keystone") (field (name "PUBLISHER") "Texas Instruments"))
      (libsource (lib "Connectors_Keystone") (part "5001"))
    )
    (comp (ref "TP108")
      (value "5001")
      (footprint "Keystone5001")
      (description "Test Point, Miniature, Black, TH")
      (fields (field (name "MANUFACTURER") "Keystone") (field (name "PUBLISHER") "Texas Instruments"))
      (libsource (lib "Connectors_Keystone") (part "5001"))
    )
    (comp (ref "TP109")
      (value "5001")
      (footprint "Keystone5001")
      (description "Test Point, Miniature, Black, TH")
      (fields (field (name "MANUFACTURER") "Keystone") (field (name "PUBLISHER") "Texas Instruments"))
      (libsource (lib "Connectors_Keystone") (part "5001"))
    )
  )
  (nets
    (net (code "1") (name "/EZFET_AVBUS") (class "Default")
      (node (ref "C123") (pin "2") (pinfunction "2_2") (pintype "passive"))
      (node (ref "MSP101") (pin "1") (pinfunction "P6.0/CB0/A0_1") (pintype "bidirectional"))
      (node (ref "R124") (pin "2") (pinfunction "2_2") (pintype "passive"))
      (node (ref "R125") (pin "1") (pinfunction "1_1") (pintype "passive"))
    )
    (net (code "2") (name "/EZFET_AVCC") (class "Default")
      (node (ref "C116") (pin "2") (pinfunction "2_2") (pintype "passive"))
      (node (ref "MSP102") (pin "6") (pinfunction "P1.5/TA0.0/SCLK/A5/CA5/TMS_6") (pintype "bidirectional"))
      (node (ref "R114") (pin "2") (pinfunction "2_2") (pintype "passive"))
      (node (ref "R115") (pin "1") (pinfunction "1_1") (pintype "passive"))
    )
    (net (code "3") (name "/EZFET_AVCCOUT") (class "Default")
      (node (ref "C115") (pin "2") (pinfunction "2_2") (pintype "passive"))
      (node (ref "MSP102") (pin "1") (pinfunction "P1.0/TA0CLK/ACLK/A0/CA0_1") (pintype "bidirectional"))
      (node (ref "R112") (pin "2") (pinfunction "2_2") (pintype "passive"))
      (node (ref "R113") (pin "1") (pinfunction "1_1") (pintype "passive"))
    )
    (net (code "4") (name "/EZFET_AVCCOUT2ADC") (class "Default")
      (node (ref "C122") (pin "2") (pinfunction "2_2") (pintype "passive"))
      (node (ref "MSP101") (pin "2") (pinfunction "P6.1/CB1/A1_2") (pintype "bidirectional"))
      (node (ref "R121") (pin "2") (pinfunction "2_2") (pintype "passive"))
      (node (ref "R122") (pin "1") (pinfunction "1_1") (pintype "passive"))
    )
    (net (code "5") (name "/EZFET_DCDCCAL0") (class "Default")
      (node (ref "MSP102") (pin "12") (pinfunction "P2.6/XIN/TA0.1_12") (pintype "bidirectional"))
      (node (ref "R126") (pin "1") (pinfunction "1_1") (pintype "passive"))
    )
    (net (code "6") (name "/EZFET_DCDCCAL1") (class "Default")
      (node (ref "MSP102") (pin "2") (pinfunction "P1.1/TA0.0/A1/CA1_2") (pintype "bidirectional"))
      (node (ref "R127") (pin "1") (pinfunction "1_1") (pintype "passive"))
    )
    (net (code "7") (name "/EZFET_DCDCCAL2") (class "Default")
      (node (ref "MSP102") (pin "11") (pinfunction "P2.7/XOUT_11") (pintype "bidirectional"))
      (node (ref "R128") (pin "2") (pinfunction "2_2") (pintype "passive"))
    )
    (net (code "8") (name "/EZFET_DCDCIO0") (class "Default")
      (node (ref "MSP101") (pin "5") (pinfunction "P6.4/CB4/A4_5") (pintype "bidirectional"))
      (node (ref "MSP102") (pin "4") (pinfunction "P1.3/ADC10CLK/CAOUT/A3/VREF-/VEREF-/CA3_4") (pintype "bidirectional"))
    )
    (net (code "9") (name "/EZFET_DCDCIO1") (class "Default")
      (node (ref "MSP101") (pin "6") (pinfunction "P6.5/CB5/A5_6") (pintype "bidirectional"))
      (node (ref "MSP102") (pin "5") (pinfunction "P1.4/SMCLK/TA0.2/A4/VREF+/VEREF+/CA4/TCK_5") (pintype "bidirectional"))
    )
    (net (code "10") (name "/EZFET_DCDCPULSE") (class "Default")
      (node (ref "MSP101") (pin "28") (pinfunction "P2.2/TA2CLK/SMCLK_28") (pintype "bidirectional"))
      (node (ref "MSP102") (pin "3") (pinfunction "P1.2/TA0.1/A2/CA2_3") (pintype "bidirectional"))
      (node (ref "R118") (pin "2") (pinfunction "2_2") (pintype "passive"))
    )
    (net (code "11") (name "/EZFET_DCDCRST") (class "Default")
      (node (ref "MSP101") (pin "7") (pinfunction "P6.6/CB6/A6_7") (pintype "bidirectional"))
      (node (ref "MSP102") (pin "9") (pinfunction "~{RST}/NMI/SBWTDIO_9") (pintype "bidirectional"))
      (node (ref "TP108") (pin "1") (pintype "passive"))
    )
    (net (code "12") (name "/EZFET_DCDCTEST") (class "Default")
      (node (ref "MSP101") (pin "8") (pinfunction "P6.7/CB7/A7_8") (pintype "bidirectional"))
      (node (ref "MSP102") (pin "10") (pinfunction "TEST/SBWTCK_10") (pintype "input"))
      (node (ref "TP109") (pin "1") (pintype "passive"))
    )
    (net (code "13") (name "/EZFET_DM") (class "Default")
      (node (ref "IC102") (pin "4") (pinfunction "IO3_4") (pintype "passive"))
      (node (ref "J102") (pin "2") (pinfunction "D-_2") (pintype "passive"))
      (node (ref "R103") (pin "1") (pinfunction "1_1") (pintype "passive"))
    )
    (net (code "14") (name "/EZFET_DP") (class "Default")
      (node (ref "IC102") (pin "1") (pinfunction "IO1_1") (pintype "passive"))
      (node (ref "J102") (pin "3") (pinfunction "D+_3") (pintype "passive"))
      (node (ref "R104") (pin "1") (pinfunction "1_1") (pintype "passive"))
    )
    (net (code "15") (name "/EZFET_HOSTSCL") (class "Default")
      (node (ref "MSP101") (pin "35") (pinfunction "P3.1/UCB0SOMI/UCB0SCL_35") (pintype "bidirectional"))
      (node (ref "MSP102") (pin "7") (pinfunction "P1.6/TA0.1/SDO/SCL/A6/CA6/TDI/TCLK_7") (pintype "bidirectional"))
      (node (ref "R117") (pin "2") (pinfunction "2_2") (pintype "passive"))
    )
    (net (code "16") (name "/EZFET_HOSTSDA") (class "Default")
      (node (ref "MSP101") (pin "34") (pinfunction "P3.0/UCB0SIMO/UCB0SDA_34") (pintype "bidirectional"))
      (node (ref "MSP102") (pin "8") (pinfunction "P1.7/CAOUT/SDI/SDA/A7/CA7/TDO/TDI_8") (pintype "bidirectional"))
      (node (ref "R116") (pin "2") (pinfunction "2_2") (pintype "passive"))
    )
    (net (code "17") (name "/EZFET_LED0") (class "Default")
      (node (ref "MSP101") (pin "20") (pinfunction "P1.2/TA0.1_20") (pintype "bidirectional"))
      (node (ref "R101") (pin "2") (pinfunction "2_2") (pintype "passive"))
    )
    (net (code "18") (name "/EZFET_LED1") (class "Default")
      (node (ref "MSP101") (pin "21") (pinfunction "P1.3/TA0.2_21") (pintype "bidirectional"))
      (node (ref "R102") (pin "2") (pinfunction "2_2") (pintype "passive"))
    )
    (net (code "19") (name "/EZFET_NC_TMSC") (class "Default")
      (node (ref "MSP101") (pin "45") (pinfunction "P4.4/PM_UCA1TXD/PM_UCA1SIMO_45") (pintype "bidirectional"))
    )
    (net (code "20") (name "/EZFET_PU.0{slash}DP") (class "Default")
      (node (ref "C111") (pin "1") (pinfunction "1_1") (pintype "passive"))
      (node (ref "MSP101") (pin "50") (pinfunction "PU.0/DP_50") (pintype "bidirectional"))
      (node (ref "R104") (pin "2") (pinfunction "2_2") (pintype "passive"))
      (node (ref "R105") (pin "2") (pinfunction "2_2") (pintype "passive"))
      (node (ref "R106") (pin "2") (pinfunction "2_2") (pintype "passive"))
    )
    (net (code "21") (name "/EZFET_PU.1{slash}DM") (class "Default")
      (node (ref "C110") (pin "1") (pinfunction "1_1") (pintype "passive"))
      (node (ref "MSP101") (pin "52") (pinfunction "PU.1/DM_52") (pintype "bidirectional"))
      (node (ref "R103") (pin "2") (pinfunction "2_2") (pintype "passive"))
    )
    (net (code "22") (name "/EZFET_PUR") (class "Default")
      (node (ref "MSP101") (pin "51") (pinfunction "PUR_51") (pintype "passive"))
      (node (ref "R105") (pin "1") (pinfunction "1_1") (pintype "passive"))
    )
    (net (code "23") (name "/EZFET_RST") (class "Default")
      (node (ref "C112") (pin "2") (pinfunction "2_2") (pintype "passive"))
      (node (ref "MSP101") (pin "64") (pinfunction "~{RST}/NMI/SBWTDIO_64") (pintype "bidirectional"))
      (node (ref "R109") (pin "2") (pinfunction "2_2") (pintype "passive"))
      (node (ref "TP107") (pin "1") (pintype "passive"))
    )
    (net (code "24") (name "/EZFET_SBWTCK") (class "Default")
      (node (ref "MSP101") (pin "44") (pinfunction "P4.3/PM_UCB1CLK/PM_UCA1STE_44") (pintype "bidirectional"))
      (node (ref "R129") (pin "1") (pinfunction "1_1") (pintype "passive"))
    )
    (net (code "25") (name "/EZFET_SBWTDIO") (class "Default")
      (node (ref "MSP101") (pin "43") (pinfunction "P4.2/PM_UCB1SOMI/PM_UCB1SCL_43") (pintype "bidirectional"))
      (node (ref "R130") (pin "1") (pinfunction "1_1") (pintype "passive"))
    )
    (net (code "26") (name "/EZFET_SHIELD") (class "Default")
      (node (ref "C126") (pin "2") (pinfunction "2_2") (pintype "passive"))
      (node (ref "IC102") (pin "5") (pinfunction "IO4_5") (pintype "passive"))
      (node (ref "J102") (pin "10") (pinfunction "10_10") (pintype "passive"))
      (node (ref "J102") (pin "11") (pinfunction "11_11") (pintype "passive"))
      (node (ref "J102") (pin "6") (pinfunction "6_6") (pintype "passive"))
      (node (ref "J102") (pin "7") (pinfunction "7_7") (pintype "passive"))
      (node (ref "J102") (pin "8") (pinfunction "8_8") (pintype "passive"))
      (node (ref "J102") (pin "9") (pinfunction "9_9") (pintype "passive"))
      (node (ref "R123") (pin "2") (pinfunction "2_2") (pintype "passive"))
    )
    (net (code "27") (name "/EZFET_TCK") (class "Default")
      (node (ref "MSP101") (pin "63") (pinfunction "PJ.3/TCK_63") (pintype "bidirectional"))
      (node (ref "TP106") (pin "1") (pintype "passive"))
    )
    (net (code "28") (name "/EZFET_TDI") (class "Default")
      (node (ref "MSP101") (pin "61") (pinfunction "PJ.1/TDI/TCLK_61") (pintype "bidirectional"))
      (node (ref "TP104") (pin "1") (pintype "passive"))
    )
    (net (code "29") (name "/EZFET_TDO") (class "Default")
      (node (ref "MSP101") (pin "60") (pinfunction "PJ.0/TDO_60") (pintype "bidirectional"))
      (node (ref "TP103") (pin "1") (pintype "passive"))
    )
    (net (code "30") (name "/EZFET_TEST") (class "Default")
      (node (ref "MSP101") (pin "59") (pinfunction "TEST/SBWTCK_59") (pintype "input"))
      (node (ref "TP102") (pin "1") (pintype "passive"))
    )
    (net (code "31") (name "/EZFET_TMS") (class "Default")
      (node (ref "MSP101") (pin "62") (pinfunction "PJ.2/TMS_62") (pintype "bidirectional"))
      (node (ref "TP105") (pin "1") (pintype "passive"))
    )
    (net (code "32") (name "/EZFET_UARTCTS") (class "Default")
      (node (ref "MSP101") (pin "32") (pinfunction "P2.6/RTCCLK/DMAE0_32") (pintype "bidirectional"))
    )
    (net (code "33") (name "/EZFET_UARTRTS") (class "Default")
      (node (ref "MSP101") (pin "33") (pinfunction "P2.7/UCB0STE/UCA0CLK_33") (pintype "bidirectional"))
    )
    (net (code "34") (name "/EZFET_UARTRXD") (class "Default")
      (node (ref "J101") (pin "5") (pinfunction "5_5") (pintype "passive"))
      (node (ref "MSP101") (pin "38") (pinfunction "P3.4/UCA0RXD/UCA0SOMI_38") (pintype "bidirectional"))
    )
    (net (code "35") (name "/EZFET_UARTTXD") (class "Default")
      (node (ref "J101") (pin "7") (pinfunction "7_7") (pintype "passive"))
      (node (ref "MSP101") (pin "37") (pinfunction "P3.3/UCA0TXD/UCA0SIMO_37") (pintype "bidirectional"))
    )
    (net (code "36") (name "/EZFET_V18") (class "Default")
      (node (ref "C102") (pin "2") (pinfunction "2_2") (pintype "passive"))
      (node (ref "MSP101") (pin "55") (pinfunction "V18_55") (pintype "passive"))
    )
    (net (code "37") (name "/EZFET_VCCEN1") (class "Default")
      (node (ref "IC103") (pin "3") (pinfunction "IN1_3") (pintype "input"))
      (node (ref "MSP101") (pin "26") (pinfunction "P2.0/TA1.1_26") (pintype "bidirectional"))
      (node (ref "R107") (pin "2") (pinfunction "2_2") (pintype "passive"))
    )
    (net (code "38") (name "/EZFET_VCCEN2") (class "Default")
      (node (ref "IC103") (pin "7") (pinfunction "IN2_7") (pintype "input"))
      (node (ref "MSP101") (pin "27") (pinfunction "P2.1/TA1.2_27") (pintype "bidirectional"))
      (node (ref "R108") (pin "2") (pinfunction "2_2") (pintype "passive"))
    )
    (net (code "39") (name "/EZFET_VREF") (class "Default")
      (node (ref "C121") (pin "2") (pinfunction "2_2") (pintype "passive"))
      (node (ref "MSP101") (pin "9") (pinfunction "P5.0/A8/VREF+/VEREF+_9") (pintype "bidirectional"))
    )
    (net (code "40") (name "/EZFET_VUSB") (class "Default")
      (node (ref "C107") (pin "2") (pinfunction "2_2") (pintype "passive"))
      (node (ref "MSP101") (pin "54") (pinfunction "VUSB_54") (pintype "power_in"))
    )
    (net (code "41") (name "3V3") (class "Default")
      (node (ref "J101") (pin "10") (pinfunction "10_10") (pintype "passive"))
    )
    (net (code "42") (name "5V0") (class "Default")
      (node (ref "J101") (pin "12") (pinfunction "12_12") (pintype "passive"))
    )
    (net (code "43") (name "BCLUART_RXD") (class "Default")
      (node (ref "J101") (pin "8") (pinfunction "8_8") (pintype "passive"))
    )
    (net (code "44") (name "BCLUART_TXD") (class "Default")
      (node (ref "J101") (pin "6") (pinfunction "6_6") (pintype "passive"))
    )
    (net (code "45") (name "EZFET_VBUS") (class "Default")
      (node (ref "C108") (pin "2") (pinfunction "2_2") (pintype "passive"))
      (node (ref "C109") (pin "1") (pinfunction "+_1") (pintype "passive"))
      (node (ref "C117") (pin "2") (pinfunction "2_2") (pintype "passive"))
      (node (ref "C118") (pin "2") (pinfunction "2_2") (pintype "passive"))
      (node (ref "C125") (pin "2") (pinfunction "2_2") (pintype "passive"))
      (node (ref "IC101") (pin "1") (pinfunction "IN_1") (pintype "power_in"))
      (node (ref "IC101") (pin "6") (pinfunction "EN_6") (pintype "input"))
      (node (ref "IC102") (pin "6") (pinfunction "VCC_6") (pintype "power_in"))
      (node (ref "IC103") (pin "2") (pinfunction "V+_2") (pintype "power_in"))
      (node (ref "J101") (pin "11") (pinfunction "11_11") (pintype "passive"))
      (node (ref "L103") (pin "2") (pinfunction "2_2") (pintype "passive"))
      (node (ref "MSP101") (pin "53") (pinfunction "VBUS_53") (pintype "power_in"))
      (node (ref "R120") (pin "2") (pinfunction "2_2") (pintype "passive"))
      (node (ref "R124") (pin "1") (pinfunction "1_1") (pintype "passive"))
      (node (ref "T101") (pin "2") (pinfunction "S_2") (pintype "passive"))
    )
    (net (code "46") (name "EZFET_VCC") (class "Default")
      (node (ref "C103") (pin "2") (pinfunction "2_2") (pintype "passive"))
      (node (ref "C104") (pin "1") (pinfunction "+_1") (pintype "passive"))
      (node (ref "C105") (pin "2") (pinfunction "2_2") (pintype "passive"))
      (node (ref "C106") (pin "1") (pinfunction "+_1") (pintype "passive"))
      (node (ref "C113") (pin "2") (pinfunction "2_2") (pintype "passive"))
      (node (ref "C114") (pin "2") (pinfunction "2_2") (pintype "passive"))
      (node (ref "C124") (pin "2") (pinfunction "2_2") (pintype "passive"))
      (node (ref "IC101") (pin "3") (pinfunction "OUT_3") (pintype "power_in"))
      (node (ref "IC103") (pin "4") (pinfunction "COM2_4") (pintype "bidirectional"))
      (node (ref "MSP101") (pin "11") (pinfunction "AVCC1_11") (pintype "power_in"))
      (node (ref "MSP101") (pin "15") (pinfunction "DVCC1_15") (pintype "power_in"))
      (node (ref "MSP101") (pin "40") (pinfunction "DVCC2_40") (pintype "power_in"))
      (node (ref "MSP102") (pin "15") (pinfunction "AVCC_15") (pintype "power_in"))
      (node (ref "MSP102") (pin "16") (pinfunction "DVCC_16") (pintype "power_in"))
      (node (ref "R109") (pin "1") (pinfunction "1_1") (pintype "passive"))
      (node (ref "R114") (pin "1") (pinfunction "1_1") (pintype "passive"))
      (node (ref "R116") (pin "1") (pinfunction "1_1") (pintype "passive"))
      (node (ref "R117") (pin "1") (pinfunction "1_1") (pintype "passive"))
    )
    (net (code "47") (name "EZFET_VCCOUT") (class "Default")
      (node (ref "C119") (pin "2") (pinfunction "2_2") (pintype "passive"))
      (node (ref "C120") (pin "2") (pinfunction "2_2") (pintype "passive"))
      (node (ref "IC103") (pin "8") (pinfunction "COM1_8") (pintype "bidirectional"))
      (node (ref "L101") (pin "2") (pinfunction "2_2") (pintype "passive"))
      (node (ref "R112") (pin "1") (pinfunction "1_1") (pintype "passive"))
      (node (ref "R121") (pin "1") (pinfunction "1_1") (pintype "passive"))
      (node (ref "R126") (pin "2") (pinfunction "2_2") (pintype "passive"))
      (node (ref "R127") (pin "2") (pinfunction "2_2") (pintype "passive"))
      (node (ref "R128") (pin "1") (pinfunction "1_1") (pintype "passive"))
    )
    (net (code "48") (name "EZFET_VCCTARGET") (class "Default")
      (node (ref "C127") (pin "1") (pinfunction "1_1") (pintype "passive"))
      (node (ref "IC103") (pin "1") (pinfunction "NO1_1") (pintype "bidirectional"))
      (node (ref "IC103") (pin "5") (pinfunction "NO2_5") (pintype "bidirectional"))
      (node (ref "J101") (pin "9") (pinfunction "9_9") (pintype "passive"))
    )
    (net (code "49") (name "EZ_GND") (class "Default")
      (node (ref "C101") (pin "1") (pinfunction "1_1") (pintype "passive"))
      (node (ref "C102") (pin "1") (pinfunction "1_1") (pintype "passive"))
      (node (ref "C103") (pin "1") (pinfunction "1_1") (pintype "passive"))
      (node (ref "C104") (pin "2") (pinfunction "-_2") (pintype "passive"))
      (node (ref "C105") (pin "1") (pinfunction "1_1") (pintype "passive"))
      (node (ref "C106") (pin "2") (pinfunction "-_2") (pintype "passive"))
      (node (ref "C107") (pin "1") (pinfunction "1_1") (pintype "passive"))
      (node (ref "C108") (pin "1") (pinfunction "1_1") (pintype "passive"))
      (node (ref "C109") (pin "2") (pinfunction "-_2") (pintype "passive"))
      (node (ref "C110") (pin "2") (pinfunction "2_2") (pintype "passive"))
      (node (ref "C111") (pin "2") (pinfunction "2_2") (pintype "passive"))
      (node (ref "C112") (pin "1") (pinfunction "1_1") (pintype "passive"))
      (node (ref "C113") (pin "1") (pinfunction "1_1") (pintype "passive"))
      (node (ref "C114") (pin "1") (pinfunction "1_1") (pintype "passive"))
      (node (ref "C115") (pin "1") (pinfunction "1_1") (pintype "passive"))
      (node (ref "C116") (pin "1") (pinfunction "1_1") (pintype "passive"))
      (node (ref "C117") (pin "1") (pinfunction "1_1") (pintype "passive"))
      (node (ref "C118") (pin "1") (pinfunction "1_1") (pintype "passive"))
      (node (ref "C119") (pin "1") (pinfunction "1_1") (pintype "passive"))
      (node (ref "C120") (pin "1") (pinfunction "1_1") (pintype "passive"))
      (node (ref "C121") (pin "1") (pinfunction "1_1") (pintype "passive"))
      (node (ref "C122") (pin "1") (pinfunction "1_1") (pintype "passive"))
      (node (ref "C123") (pin "1") (pinfunction "1_1") (pintype "passive"))
      (node (ref "C124") (pin "1") (pinfunction "1_1") (pintype "passive"))
      (node (ref "C125") (pin "1") (pinfunction "1_1") (pintype "passive"))
      (node (ref "C126") (pin "1") (pinfunction "1_1") (pintype "passive"))
      (node (ref "C127") (pin "2") (pinfunction "2_2") (pintype "passive"))
      (node (ref "D102") (pin "1") (pinfunction "A_1") (pintype "passive"))
      (node (ref "D102") (pin "2") (pinfunction "A_2") (pintype "passive"))
      (node (ref "IC101") (pin "2") (pinfunction "GND_2") (pintype "power_in"))
      (node (ref "IC102") (pin "3") (pinfunction "GND_3") (pintype "power_in"))
      (node (ref "IC103") (pin "6") (pinfunction "GND_6") (pintype "power_in"))
      (node (ref "J101") (pin "13") (pinfunction "13_13") (pintype "passive"))
      (node (ref "L102") (pin "2") (pinfunction "2_2") (pintype "passive"))
      (node (ref "LED101") (pin "2") (pinfunction "K_2") (pintype "passive"))
      (node (ref "LED102") (pin "2") (pinfunction "K_2") (pintype "passive"))
      (node (ref "MSP101") (pin "14") (pinfunction "AVSS1_14") (pintype "power_in"))
      (node (ref "MSP101") (pin "16") (pinfunction "DVSS1_16") (pintype "power_in"))
      (node (ref "MSP101") (pin "39") (pinfunction "DVSS2_39") (pintype "power_in"))
      (node (ref "MSP101") (pin "49") (pinfunction "VSSU_49") (pintype "power_in"))
      (node (ref "MSP101") (pin "56") (pinfunction "AVSS2_56") (pintype "power_in"))
      (node (ref "MSP101") (pin "65") (pinfunction "QFN_PAD_65") (pintype "power_in"))
      (node (ref "MSP102") (pin "13") (pinfunction "AVSS_13") (pintype "power_in"))
      (node (ref "MSP102") (pin "14") (pinfunction "DVSS_14") (pintype "power_in"))
      (node (ref "MSP102") (pin "17") (pinfunction "QFN_PAD_17") (pintype "power_in"))
      (node (ref "Q101") (pin "2") (pinfunction "GND_2") (pintype "passive"))
      (node (ref "R106") (pin "1") (pinfunction "1_1") (pintype "passive"))
      (node (ref "R107") (pin "1") (pinfunction "1_1") (pintype "passive"))
      (node (ref "R108") (pin "1") (pinfunction "1_1") (pintype "passive"))
      (node (ref "R113") (pin "2") (pinfunction "2_2") (pintype "passive"))
      (node (ref "R115") (pin "2") (pinfunction "2_2") (pintype "passive"))
      (node (ref "R119") (pin "1") (pinfunction "1_1") (pintype "passive"))
      (node (ref "R122") (pin "2") (pinfunction "2_2") (pintype "passive"))
      (node (ref "R123") (pin "1") (pinfunction "1_1") (pintype "passive"))
      (node (ref "R125") (pin "2") (pinfunction "2_2") (pintype "passive"))
      (node (ref "TP101") (pin "1") (pintype "passive"))
    )
    (net (code "50") (name "GND") (class "Default")
      (node (ref "J101") (pin "14") (pinfunction "14_14") (pintype "passive"))
    )
    (net (code "51") (name "Net-(D101-K)") (class "Default")
      (node (ref "D101") (pin "3") (pinfunction "K_3") (pintype "passive"))
      (node (ref "R120") (pin "1") (pinfunction "1_1") (pintype "passive"))
      (node (ref "T101") (pin "1") (pinfunction "G_1") (pintype "passive"))
      (node (ref "T102") (pin "3") (pinfunction "C_3") (pintype "passive"))
    )
    (net (code "52") (name "Net-(D102-K)") (class "Default")
      (node (ref "D102") (pin "3") (pinfunction "K_3") (pintype "passive"))
      (node (ref "L101") (pin "1") (pinfunction "1_1") (pintype "passive"))
      (node (ref "T101") (pin "3") (pinfunction "D_3") (pintype "passive"))
    )
    (net (code "53") (name "Net-(J101-Pad1)") (class "Default")
      (node (ref "J101") (pin "1") (pinfunction "1_1") (pintype "passive"))
      (node (ref "R129") (pin "2") (pinfunction "2_2") (pintype "passive"))
    )
    (net (code "54") (name "Net-(J101-Pad3)") (class "Default")
      (node (ref "J101") (pin "3") (pinfunction "3_3") (pintype "passive"))
      (node (ref "R130") (pin "2") (pinfunction "2_2") (pintype "passive"))
    )
    (net (code "55") (name "Net-(J102-GND)") (class "Default")
      (node (ref "J102") (pin "5") (pinfunction "GND_5") (pintype "passive"))
      (node (ref "L102") (pin "1") (pinfunction "1_1") (pintype "passive"))
    )
    (net (code "56") (name "Net-(J102-VBUS)") (class "Default")
      (node (ref "J102") (pin "1") (pinfunction "VBUS_1") (pintype "passive"))
      (node (ref "L103") (pin "1") (pinfunction "1_1") (pintype "passive"))
    )
    (net (code "57") (name "Net-(LED101-A)") (class "Default")
      (node (ref "LED101") (pin "1") (pinfunction "A_1") (pintype "passive"))
      (node (ref "R101") (pin "1") (pinfunction "1_1") (pintype "passive"))
    )
    (net (code "58") (name "Net-(LED102-A)") (class "Default")
      (node (ref "LED102") (pin "1") (pinfunction "A_1") (pintype "passive"))
      (node (ref "R102") (pin "1") (pinfunction "1_1") (pintype "passive"))
    )
    (net (code "59") (name "Net-(MSP101-P5.2{slash}XT2IN)") (class "Default")
      (node (ref "MSP101") (pin "57") (pinfunction "P5.2/XT2IN_57") (pintype "bidirectional"))
      (node (ref "Q101") (pin "1") (pinfunction "In_1") (pintype "passive"))
    )
    (net (code "60") (name "Net-(MSP101-P5.3{slash}XT2OUT)") (class "Default")
      (node (ref "MSP101") (pin "58") (pinfunction "P5.3/XT2OUT_58") (pintype "bidirectional"))
      (node (ref "Q101") (pin "3") (pinfunction "Out_3") (pintype "passive"))
    )
    (net (code "61") (name "Net-(MSP101-VCORE)") (class "Default")
      (node (ref "C101") (pin "2") (pinfunction "2_2") (pintype "passive"))
      (node (ref "MSP101") (pin "17") (pinfunction "VCORE_17") (pintype "passive"))
    )
    (net (code "62") (name "Net-(T102-B)") (class "Default")
      (node (ref "D101") (pin "1") (pinfunction "A_1") (pintype "passive"))
      (node (ref "D101") (pin "2") (pinfunction "A_2") (pintype "passive"))
      (node (ref "R118") (pin "1") (pinfunction "1_1") (pintype "passive"))
      (node (ref "T102") (pin "1") (pinfunction "B_1") (pintype "passive"))
    )
    (net (code "63") (name "Net-(T102-E)") (class "Default")
      (node (ref "R119") (pin "2") (pinfunction "2_2") (pintype "passive"))
      (node (ref "T102") (pin "2") (pinfunction "E_2") (pintype "passive"))
    )
    (net (code "64") (name "RST{slash}SBWTDIO") (class "Default")
      (node (ref "J101") (pin "4") (pinfunction "4_4") (pintype "passive"))
    )
    (net (code "65") (name "TST{slash}SBWTCK") (class "Default")
      (node (ref "J101") (pin "2") (pinfunction "2_2") (pintype "passive"))
    )
    (net (code "66") (name "unconnected-(IC101-NC-Pad4)") (class "Default")
      (node (ref "IC101") (pin "4") (pinfunction "NC_4") (pintype "passive"))
    )
    (net (code "67") (name "unconnected-(IC101-NC-Pad5)") (class "Default")
      (node (ref "IC101") (pin "5") (pinfunction "NC_5") (pintype "passive"))
    )
    (net (code "68") (name "unconnected-(IC102-IO2-Pad2)") (class "Default")
      (node (ref "IC102") (pin "2") (pinfunction "IO2_2") (pintype "passive"))
    )
    (net (code "69") (name "unconnected-(J102-ID-Pad4)") (class "Default")
      (node (ref "J102") (pin "4") (pinfunction "ID_4") (pintype "passive"))
    )
    (net (code "70") (name "unconnected-(MSP101-P1.0{slash}TA0CLK{slash}ACLK-Pad18)") (class "Default")
      (node (ref "MSP101") (pin "18") (pinfunction "P1.0/TA0CLK/ACLK_18") (pintype "bidirectional"))
    )
    (net (code "71") (name "unconnected-(MSP101-P1.1{slash}TA0.0-Pad19)") (class "Default")
      (node (ref "MSP101") (pin "19") (pinfunction "P1.1/TA0.0_19") (pintype "bidirectional"))
    )
    (net (code "72") (name "unconnected-(MSP101-P1.4{slash}TA0.3-Pad22)") (class "Default")
      (node (ref "MSP101") (pin "22") (pinfunction "P1.4/TA0.3_22") (pintype "bidirectional"))
    )
    (net (code "73") (name "unconnected-(MSP101-P1.5{slash}TA0.4-Pad23)") (class "Default")
      (node (ref "MSP101") (pin "23") (pinfunction "P1.5/TA0.4_23") (pintype "bidirectional"))
    )
    (net (code "74") (name "unconnected-(MSP101-P1.6{slash}TA1CLK{slash}CBOUT-Pad24)") (class "Default")
      (node (ref "MSP101") (pin "24") (pinfunction "P1.6/TA1CLK/CBOUT_24") (pintype "bidirectional"))
    )
    (net (code "75") (name "unconnected-(MSP101-P1.7{slash}TA1.0-Pad25)") (class "Default")
      (node (ref "MSP101") (pin "25") (pinfunction "P1.7/TA1.0_25") (pintype "bidirectional"))
    )
    (net (code "76") (name "unconnected-(MSP101-P2.3{slash}TA2.0-Pad29)") (class "Default")
      (node (ref "MSP101") (pin "29") (pinfunction "P2.3/TA2.0_29") (pintype "bidirectional"))
    )
    (net (code "77") (name "unconnected-(MSP101-P2.4{slash}TA2.1-Pad30)") (class "Default")
      (node (ref "MSP101") (pin "30") (pinfunction "P2.4/TA2.1_30") (pintype "bidirectional"))
    )
    (net (code "78") (name "unconnected-(MSP101-P2.5{slash}TA2.2-Pad31)") (class "Default")
      (node (ref "MSP101") (pin "31") (pinfunction "P2.5/TA2.2_31") (pintype "bidirectional"))
    )
    (net (code "79") (name "unconnected-(MSP101-P3.2{slash}UCB0CLK{slash}UCA0STE-Pad36)") (class "Default")
      (node (ref "MSP101") (pin "36") (pinfunction "P3.2/UCB0CLK/UCA0STE_36") (pintype "bidirectional"))
    )
    (net (code "80") (name "unconnected-(MSP101-P4.0{slash}PM_UCB1STE{slash}PM_UCA1CLK-Pad41)") (class "Default")
      (node (ref "MSP101") (pin "41") (pinfunction "P4.0/PM_UCB1STE/PM_UCA1CLK_41") (pintype "bidirectional"))
    )
    (net (code "81") (name "unconnected-(MSP101-P4.1{slash}PM_UCB1SIMO{slash}PM_UCB1SDA-Pad42)") (class "Default")
      (node (ref "MSP101") (pin "42") (pinfunction "P4.1/PM_UCB1SIMO/PM_UCB1SDA_42") (pintype "bidirectional"))
    )
    (net (code "82") (name "unconnected-(MSP101-P4.5{slash}PM_UCA1RXD{slash}PM_UCA1SOMI-Pad46)") (class "Default")
      (node (ref "MSP101") (pin "46") (pinfunction "P4.5/PM_UCA1RXD/PM_UCA1SOMI_46") (pintype "bidirectional"))
    )
    (net (code "83") (name "unconnected-(MSP101-P4.6{slash}PM_NONE-Pad47)") (class "Default")
      (node (ref "MSP101") (pin "47") (pinfunction "P4.6/PM_NONE_47") (pintype "bidirectional"))
    )
    (net (code "84") (name "unconnected-(MSP101-P4.7{slash}PM_NONE-Pad48)") (class "Default")
      (node (ref "MSP101") (pin "48") (pinfunction "P4.7/PM_NONE_48") (pintype "bidirectional"))
    )
    (net (code "85") (name "unconnected-(MSP101-P5.1{slash}A9{slash}VREF-{slash}VEREF--Pad10)") (class "Default")
      (node (ref "MSP101") (pin "10") (pinfunction "P5.1/A9/VREF-/VEREF-_10") (pintype "bidirectional"))
    )
    (net (code "86") (name "unconnected-(MSP101-P5.4{slash}XIN-Pad12)") (class "Default")
      (node (ref "MSP101") (pin "12") (pinfunction "P5.4/XIN_12") (pintype "bidirectional"))
    )
    (net (code "87") (name "unconnected-(MSP101-P5.5{slash}XOUT-Pad13)") (class "Default")
      (node (ref "MSP101") (pin "13") (pinfunction "P5.5/XOUT_13") (pintype "bidirectional"))
    )
    (net (code "88") (name "unconnected-(MSP101-P6.2{slash}CB2{slash}A2-Pad3)") (class "Default")
      (node (ref "MSP101") (pin "3") (pinfunction "P6.2/CB2/A2_3") (pintype "bidirectional"))
    )
    (net (code "89") (name "unconnected-(MSP101-P6.3{slash}CB3{slash}A3-Pad4)") (class "Default")
      (node (ref "MSP101") (pin "4") (pinfunction "P6.3/CB3/A3_4") (pintype "bidirectional"))
    )
  )
)
